# vib_belt.net
KiCad netlist of a schematic drawn in EAGLE
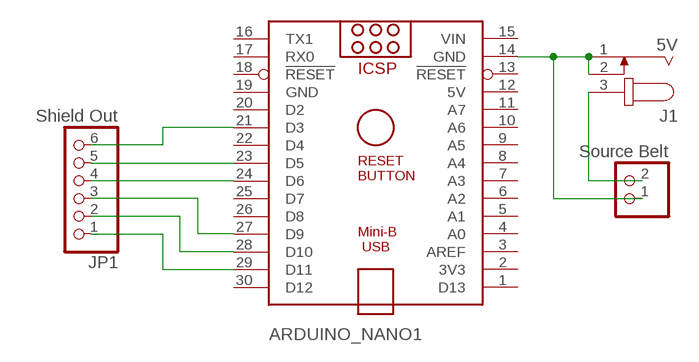
[diagram p0: schematic, sheet 1]

(export (version "E")
  (design (tool "Eeschema 10.0.6"))
  (components
    (comp (ref "ARDUINO_NANO1")
      (value "ARDUINO_NANO")
      (footprint "eagle-import:ARDUINO_NANO")
      (libsource (lib "eagle-import") (part "ARDUINO_NANO"))
    )
    (comp (ref "J1")
      (value "5V")
      (footprint "eagle-import:SPC4077")
      (libsource (lib "eagle-import") (part "JACK-PLUG0"))
    )
    (comp (ref "JP1")
      (value "Shield Out")
      (footprint "eagle-import:1X06_90")
      (libsource (lib "eagle-import") (part "PINHD-1X6/90"))
    )
    (comp (ref "JP2")
      (value "Source Belt")
      (footprint "eagle-import:1X02_90")
      (libsource (lib "eagle-import") (part "PINHD-1X2/90"))
    )
  )
  (nets
    (net (code "1") (name "/5V") (class "Default")
      (node (ref "ARDUINO_NANO1") (pin "12") (pinfunction "5V_12") (pintype "power_in"))
    )
    (net (code "2") (name "/GND") (class "Default")
      (node (ref "ARDUINO_NANO1") (pin "19") (pinfunction "GND_19") (pintype "power_in"))
    )
    (net (code "3") (name "/VIN") (class "Default")
      (node (ref "ARDUINO_NANO1") (pin "15") (pinfunction "VIN_15") (pintype "power_in"))
    )
    (net (code "4") (name "Net-(ARDUINO_NANO1-D3)") (class "Default")
      (node (ref "ARDUINO_NANO1") (pin "21") (pinfunction "D3_21") (pintype "bidirectional"))
      (node (ref "JP1") (pin "6") (pinfunction "6_6") (pintype "passive"))
    )
    (net (code "5") (name "Net-(ARDUINO_NANO1-D5)") (class "Default")
      (node (ref "ARDUINO_NANO1") (pin "23") (pinfunction "D5_23") (pintype "bidirectional"))
      (node (ref "JP1") (pin "5") (pinfunction "5_5") (pintype "passive"))
    )
    (net (code "6") (name "Net-(ARDUINO_NANO1-D6)") (class "Default")
      (node (ref "ARDUINO_NANO1") (pin "24") (pinfunction "D6_24") (pintype "bidirectional"))
      (node (ref "JP1") (pin "4") (pinfunction "4_4") (pintype "passive"))
    )
    (net (code "7") (name "Net-(ARDUINO_NANO1-D9)") (class "Default")
      (node (ref "ARDUINO_NANO1") (pin "27") (pinfunction "D9_27") (pintype "bidirectional"))
      (node (ref "JP1") (pin "3") (pinfunction "3_3") (pintype "passive"))
    )
    (net (code "8") (name "Net-(ARDUINO_NANO1-D10)") (class "Default")
      (node (ref "ARDUINO_NANO1") (pin "28") (pinfunction "D10_28") (pintype "bidirectional"))
      (node (ref "JP1") (pin "2") (pinfunction "2_2") (pintype "passive"))
    )
    (net (code "9") (name "Net-(ARDUINO_NANO1-D11)") (class "Default")
      (node (ref "ARDUINO_NANO1") (pin "29") (pinfunction "D11_29") (pintype "bidirectional"))
      (node (ref "JP1") (pin "1") (pinfunction "1_1") (pintype "passive"))
    )
    (net (code "10") (name "Net-(ARDUINO_NANO1-GND-Pad14)") (class "Default")
      (node (ref "ARDUINO_NANO1") (pin "14") (pinfunction "GND_14") (pintype "power_in"))
      (node (ref "J1") (pin "1") (pinfunction "1_1") (pintype "passive"))
      (node (ref "J1") (pin "2") (pinfunction "2_2") (pintype "passive"))
      (node (ref "JP2") (pin "1") (pinfunction "1_1") (pintype "passive"))
    )
    (net (code "11") (name "Net-(J1-Pad3)") (class "Default")
      (node (ref "J1") (pin "3") (pinfunction "3_3") (pintype "passive"))
      (node (ref "JP2") (pin "2") (pinfunction "2_2") (pintype "passive"))
    )
    (net (code "12") (name "unconnected-(ARDUINO_NANO1-3V3-Pad2)") (class "Default")
      (node (ref "ARDUINO_NANO1") (pin "2") (pinfunction "3V3_2") (pintype "output"))
    )
    (net (code "13") (name "unconnected-(ARDUINO_NANO1-A0-Pad4)") (class "Default")
      (node (ref "ARDUINO_NANO1") (pin "4") (pinfunction "A0_4") (pintype "bidirectional"))
    )
    (net (code "14") (name "unconnected-(ARDUINO_NANO1-A1-Pad5)") (class "Default")
      (node (ref "ARDUINO_NANO1") (pin "5") (pinfunction "A1_5") (pintype "bidirectional"))
    )
    (net (code "15") (name "unconnected-(ARDUINO_NANO1-A2-Pad6)") (class "Default")
      (node (ref "ARDUINO_NANO1") (pin "6") (pinfunction "A2_6") (pintype "bidirectional"))
    )
    (net (code "16") (name "unconnected-(ARDUINO_NANO1-A3-Pad7)") (class "Default")
      (node (ref "ARDUINO_NANO1") (pin "7") (pinfunction "A3_7") (pintype "bidirectional"))
    )
    (net (code "17") (name "unconnected-(ARDUINO_NANO1-A4-Pad8)") (class "Default")
      (node (ref "ARDUINO_NANO1") (pin "8") (pinfunction "A4_8") (pintype "bidirectional"))
    )
    (net (code "18") (name "unconnected-(ARDUINO_NANO1-A5-Pad9)") (class "Default")
      (node (ref "ARDUINO_NANO1") (pin "9") (pinfunction "A5_9") (pintype "bidirectional"))
    )
    (net (code "19") (name "unconnected-(ARDUINO_NANO1-A6-Pad10)") (class "Default")
      (node (ref "ARDUINO_NANO1") (pin "10") (pinfunction "A6_10") (pintype "bidirectional"))
    )
    (net (code "20") (name "unconnected-(ARDUINO_NANO1-A7-Pad11)") (class "Default")
      (node (ref "ARDUINO_NANO1") (pin "11") (pinfunction "A7_11") (pintype "bidirectional"))
    )
    (net (code "21") (name "unconnected-(ARDUINO_NANO1-AREF-Pad3)") (class "Default")
      (node (ref "ARDUINO_NANO1") (pin "3") (pinfunction "AREF_3") (pintype "input"))
    )
    (net (code "22") (name "unconnected-(ARDUINO_NANO1-D2-Pad20)") (class "Default")
      (node (ref "ARDUINO_NANO1") (pin "20") (pinfunction "D2_20") (pintype "bidirectional"))
    )
    (net (code "23") (name "unconnected-(ARDUINO_NANO1-D4-Pad22)") (class "Default")
      (node (ref "ARDUINO_NANO1") (pin "22") (pinfunction "D4_22") (pintype "bidirectional"))
    )
    (net (code "24") (name "unconnected-(ARDUINO_NANO1-D7-Pad25)") (class "Default")
      (node (ref "ARDUINO_NANO1") (pin "25") (pinfunction "D7_25") (pintype "bidirectional"))
    )
    (net (code "25") (name "unconnected-(ARDUINO_NANO1-D8-Pad26)") (class "Default")
      (node (ref "ARDUINO_NANO1") (pin "26") (pinfunction "D8_26") (pintype "bidirectional"))
    )
    (net (code "26") (name "unconnected-(ARDUINO_NANO1-D12-Pad30)") (class "Default")
      (node (ref "ARDUINO_NANO1") (pin "30") (pinfunction "D12_30") (pintype "bidirectional"))
    )
    (net (code "27") (name "unconnected-(ARDUINO_NANO1-D13-Pad1)") (class "Default")
      (node (ref "ARDUINO_NANO1") (pin "1") (pinfunction "D13_1") (pintype "bidirectional"))
    )
    (net (code "28") (name "unconnected-(ARDUINO_NANO1-RX0-Pad17)") (class "Default")
      (node (ref "ARDUINO_NANO1") (pin "17") (pinfunction "RX0_17") (pintype "bidirectional"))
    )
    (net (code "29") (name "unconnected-(ARDUINO_NANO1-TX1-Pad16)") (class "Default")
      (node (ref "ARDUINO_NANO1") (pin "16") (pinfunction "TX1_16") (pintype "bidirectional"))
    )
    (net (code "30") (name "unconnected-(ARDUINO_NANO1-~{RESET}-Pad13)") (class "Default")
      (node (ref "ARDUINO_NANO1") (pin "13") (pinfunction "~{RESET}_13") (pintype "input"))
    )
    (net (code "31") (name "unconnected-(ARDUINO_NANO1-~{RESET}-Pad18)") (class "Default")
      (node (ref "ARDUINO_NANO1") (pin "18") (pinfunction "~{RESET}_18") (pintype "input"))
    )
  )
)
